# OpenDriver.net
KiCad netlist of a schematic drawn in Altium Designer
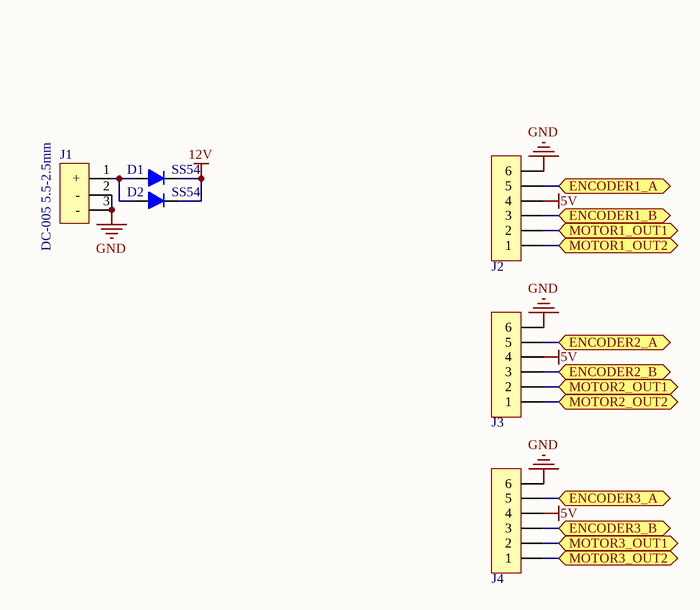
[diagram p0: OpenDriver.SchDoc]

(export (version "E")
  (design (tool "Eeschema 10.0.6"))
  (components
    (comp (ref "D1")
      (value "SS54")
      (footprint "LC-SMA(DO-214AC)_S2")
      (libsource (lib "weifengdq") (part "Diode1"))
    )
    (comp (ref "D2")
      (value "SS54")
      (footprint "LC-SMA(DO-214AC)_S2")
      (libsource (lib "weifengdq") (part "Diode1"))
    )
    (comp (ref "J1")
      (value "DC-005 5.5-2.5mm")
      (footprint "DC10B")
      (libsource (lib "weifengdq") (part "DC-005"))
    )
    (comp (ref "J2") (value "PH2.0-6P") (footprint "PH-6P") (libsource (lib "weifengdq") (part "PH2.0_6P")))
    (comp (ref "J3") (value "PH2.0-6P") (footprint "PH-6P") (libsource (lib "weifengdq") (part "PH2.0_6P")))
    (comp (ref "J4") (value "PH2.0-6P") (footprint "PH-6P") (libsource (lib "weifengdq") (part "PH2.0_6P")))
  )
  (nets
    (net (code "1") (name "/ENCODER1_A") (class "Default")
      (node (ref "J2") (pin "5") (pinfunction "5_5") (pintype "passive"))
    )
    (net (code "2") (name "/ENCODER1_B") (class "Default")
      (node (ref "J2") (pin "3") (pinfunction "3_3") (pintype "passive"))
    )
    (net (code "3") (name "/ENCODER2_A") (class "Default")
      (node (ref "J3") (pin "5") (pinfunction "5_5") (pintype "passive"))
    )
    (net (code "4") (name "/ENCODER2_B") (class "Default")
      (node (ref "J3") (pin "3") (pinfunction "3_3") (pintype "passive"))
    )
    (net (code "5") (name "/ENCODER3_A") (class "Default")
      (node (ref "J4") (pin "5") (pinfunction "5_5") (pintype "passive"))
    )
    (net (code "6") (name "/ENCODER3_B") (class "Default")
      (node (ref "J4") (pin "3") (pinfunction "3_3") (pintype "passive"))
    )
    (net (code "7") (name "/MOTOR1_OUT1") (class "Default")
      (node (ref "J2") (pin "2") (pinfunction "2_2") (pintype "passive"))
    )
    (net (code "8") (name "/MOTOR1_OUT2") (class "Default")
      (node (ref "J2") (pin "1") (pinfunction "1_1") (pintype "passive"))
    )
    (net (code "9") (name "/MOTOR2_OUT1") (class "Default")
      (node (ref "J3") (pin "2") (pinfunction "2_2") (pintype "passive"))
    )
    (net (code "10") (name "/MOTOR2_OUT2") (class "Default")
      (node (ref "J3") (pin "1") (pinfunction "1_1") (pintype "passive"))
    )
    (net (code "11") (name "/MOTOR3_OUT1") (class "Default")
      (node (ref "J4") (pin "2") (pinfunction "2_2") (pintype "passive"))
    )
    (net (code "12") (name "/MOTOR3_OUT2") (class "Default")
      (node (ref "J4") (pin "1") (pinfunction "1_1") (pintype "passive"))
    )
    (net (code "13") (name "5V") (class "Default")
      (node (ref "J2") (pin "4") (pinfunction "4_4") (pintype "passive"))
      (node (ref "J3") (pin "4") (pinfunction "4_4") (pintype "passive"))
      (node (ref "J4") (pin "4") (pinfunction "4_4") (pintype "passive"))
    )
    (net (code "14") (name "12V") (class "Default")
      (node (ref "D1") (pin "2") (pinfunction "K_2") (pintype "passive"))
      (node (ref "D2") (pin "2") (pinfunction "K_2") (pintype "passive"))
    )
    (net (code "15") (name "GND") (class "Default")
      (node (ref "J1") (pin "2") (pinfunction "-_2") (pintype "passive"))
      (node (ref "J1") (pin "3") (pinfunction "-_3") (pintype "passive"))
      (node (ref "J2") (pin "6") (pinfunction "6_6") (pintype "passive"))
      (node (ref "J3") (pin "6") (pinfunction "6_6") (pintype "passive"))
      (node (ref "J4") (pin "6") (pinfunction "6_6") (pintype "passive"))
    )
    (net (code "16") (name "Net-(D1-A)") (class "Default")
      (node (ref "D1") (pin "1") (pinfunction "A_1") (pintype "passive"))
      (node (ref "D2") (pin "1") (pinfunction "A_1") (pintype "passive"))
      (node (ref "J1") (pin "1") (pinfunction "+_1") (pintype "passive"))
    )
  )
)
